# bus-main.net
KiCad netlist of a schematic drawn in Altium Designer
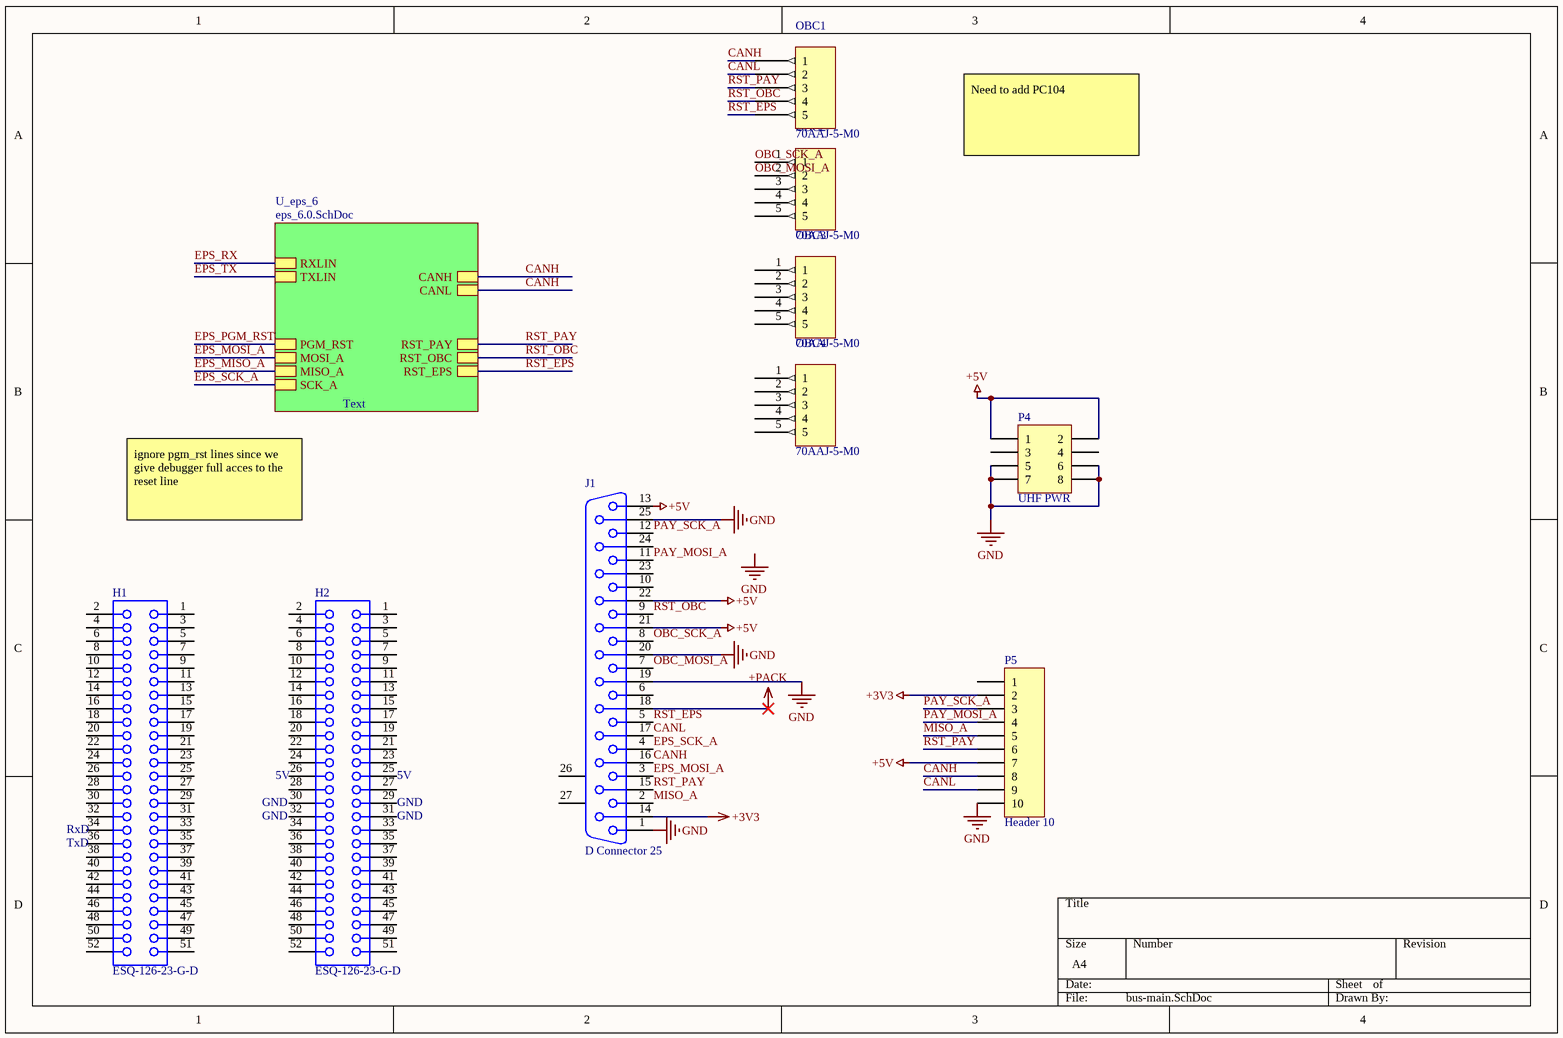
[diagram p0: bus-main.SchDoc]

(export (version "E")
  (design (tool "Eeschema 10.0.6"))
  (components
    (comp (ref "H1")
      (value "ESQ-126-23-G-D")
      (footprint "SMTC-ESQ-126-23-X-D")
      (fields (field (name "MANUFACTURER") "Samtec"))
      (libsource (lib "CONNs") (part "ESQ-126-23-G-D"))
    )
    (comp (ref "H2")
      (value "ESQ-126-23-G-D")
      (footprint "SMTC-ESQ-126-23-X-D")
      (fields (field (name "MANUFACTURER") "Samtec"))
      (libsource (lib "CONNs") (part "ESQ-126-23-G-D"))
    )
    (comp (ref "J1")
      (value "D Connector 25")
      (footprint "Mini DSub Connector")
      (description "Receptacle Assembly, 25 Position, Right Angle")
      (fields (field (name "PUBLISHER") "Altium Limited"))
      (libsource (lib "Miscellaneous Connectors") (part "D Connector 25"))
    )
    (comp (ref "OBC1") (value "70AAJ-5-M0") (libsource (lib "") (part "70AAJ-5-M0_1")))
    (comp (ref "OBC2") (value "70AAJ-5-M0") (libsource (lib "CONNs.") (part "70AAJ-5-M0")))
    (comp (ref "OBC3") (value "70AAJ-5-M0") (libsource (lib "CONNs.") (part "70AAJ-5-M0")))
    (comp (ref "OBC4") (value "70AAJ-5-M0") (libsource (lib "CONNs.") (part "70AAJ-5-M0")))
    (comp (ref "P4")
      (value "UHF PWR")
      (footprint "HDR2X4")
      (description "Header, 4-Pin, Dual row")
      (fields (field (name "PUBLISHER") "Altium Limited"))
      (libsource (lib "Miscellaneous Connectors") (part "Header 4X2"))
    )
    (comp (ref "P5")
      (value "Header 10")
      (footprint "DF14-10P-1.25H(55) - duplicate")
      (description "Header, 10-Pin")
      (fields (field (name "PUBLISHER") "Altium Limited"))
      (libsource (lib "Miscellaneous Connectors") (part "Header 10"))
    )
  )
  (nets
    (net (code "1") (name "+3V3") (class "Default")
      (node (ref "J1") (pin "14") (pinfunction "14_14") (pintype "passive"))
      (node (ref "P5") (pin "2") (pinfunction "2_2") (pintype "passive"))
    )
    (net (code "2") (name "+5V") (class "Default")
      (node (ref "J1") (pin "13") (pinfunction "13_13") (pintype "passive"))
      (node (ref "J1") (pin "21") (pinfunction "21_21") (pintype "passive"))
      (node (ref "J1") (pin "22") (pinfunction "22_22") (pintype "passive"))
      (node (ref "P4") (pin "1") (pinfunction "1_1") (pintype "passive"))
      (node (ref "P4") (pin "2") (pinfunction "2_2") (pintype "passive"))
      (node (ref "P5") (pin "7") (pinfunction "7_7") (pintype "passive"))
    )
    (net (code "3") (name "+PACK") (class "Default")
      (node (ref "J1") (pin "18") (pinfunction "18_18") (pintype "passive"))
    )
    (net (code "4") (name "/CANH") (class "Default")
      (node (ref "J1") (pin "16") (pinfunction "16_16") (pintype "passive"))
      (node (ref "OBC1") (pin "1") (pinfunction "1_1") (pintype "output"))
      (node (ref "P5") (pin "8") (pinfunction "8_8") (pintype "passive"))
    )
    (net (code "5") (name "/CANL") (class "Default")
      (node (ref "J1") (pin "17") (pinfunction "17_17") (pintype "passive"))
      (node (ref "OBC1") (pin "2") (pinfunction "2_2") (pintype "output"))
      (node (ref "P5") (pin "9") (pinfunction "9_9") (pintype "passive"))
    )
    (net (code "7") (name "/EPS_MOSI_A") (class "Default")
      (node (ref "J1") (pin "3") (pinfunction "3_3") (pintype "passive"))
    )
    (net (code "10") (name "/EPS_SCK_A") (class "Default")
      (node (ref "J1") (pin "4") (pinfunction "4_4") (pintype "passive"))
    )
    (net (code "12") (name "/MISO_A") (class "Default")
      (node (ref "J1") (pin "2") (pinfunction "2_2") (pintype "passive"))
      (node (ref "P5") (pin "5") (pinfunction "5_5") (pintype "passive"))
    )
    (net (code "13") (name "/OBC_MOSI_A") (class "Default")
      (node (ref "J1") (pin "7") (pinfunction "7_7") (pintype "passive"))
      (node (ref "OBC2") (pin "2") (pinfunction "2_2") (pintype "output"))
    )
    (net (code "14") (name "/OBC_SCK_A") (class "Default")
      (node (ref "J1") (pin "8") (pinfunction "8_8") (pintype "passive"))
      (node (ref "OBC2") (pin "1") (pinfunction "1_1") (pintype "output"))
    )
    (net (code "15") (name "/PAY_MOSI_A") (class "Default")
      (node (ref "J1") (pin "11") (pinfunction "11_11") (pintype "passive"))
      (node (ref "P5") (pin "4") (pinfunction "4_4") (pintype "passive"))
    )
    (net (code "16") (name "/PAY_SCK_A") (class "Default")
      (node (ref "J1") (pin "12") (pinfunction "12_12") (pintype "passive"))
      (node (ref "P5") (pin "3") (pinfunction "3_3") (pintype "passive"))
    )
    (net (code "17") (name "/RST_EPS") (class "Default")
      (node (ref "J1") (pin "5") (pinfunction "5_5") (pintype "passive"))
      (node (ref "OBC1") (pin "5") (pinfunction "5_5") (pintype "output"))
    )
    (net (code "18") (name "/RST_OBC") (class "Default")
      (node (ref "J1") (pin "9") (pinfunction "9_9") (pintype "passive"))
      (node (ref "OBC1") (pin "4") (pinfunction "4_4") (pintype "output"))
    )
    (net (code "19") (name "/RST_PAY") (class "Default")
      (node (ref "J1") (pin "15") (pinfunction "15_15") (pintype "passive"))
      (node (ref "OBC1") (pin "3") (pinfunction "3_3") (pintype "output"))
      (node (ref "P5") (pin "6") (pinfunction "6_6") (pintype "passive"))
    )
    (net (code "20") (name "GND") (class "Default")
      (node (ref "J1") (pin "1") (pinfunction "1_1") (pintype "passive"))
      (node (ref "J1") (pin "19") (pinfunction "19_19") (pintype "passive"))
      (node (ref "J1") (pin "20") (pinfunction "20_20") (pintype "passive"))
      (node (ref "J1") (pin "25") (pinfunction "25_25") (pintype "passive"))
      (node (ref "P4") (pin "5") (pinfunction "5_5") (pintype "passive"))
      (node (ref "P4") (pin "6") (pinfunction "6_6") (pintype "passive"))
      (node (ref "P4") (pin "7") (pinfunction "7_7") (pintype "passive"))
      (node (ref "P4") (pin "8") (pinfunction "8_8") (pintype "passive"))
      (node (ref "P5") (pin "10") (pinfunction "10_10") (pintype "passive"))
    )
    (net (code "21") (name "unconnected-(H1-Pad1)") (class "Default")
      (node (ref "H1") (pin "1") (pinfunction "1_1") (pintype "passive"))
    )
    (net (code "22") (name "unconnected-(H1-Pad2)") (class "Default")
      (node (ref "H1") (pin "2") (pinfunction "2_2") (pintype "passive"))
    )
    (net (code "23") (name "unconnected-(H1-Pad3)") (class "Default")
      (node (ref "H1") (pin "3") (pinfunction "3_3") (pintype "passive"))
    )
    (net (code "24") (name "unconnected-(H1-Pad4)") (class "Default")
      (node (ref "H1") (pin "4") (pinfunction "4_4") (pintype "passive"))
    )
    (net (code "25") (name "unconnected-(H1-Pad5)") (class "Default")
      (node (ref "H1") (pin "5") (pinfunction "5_5") (pintype "passive"))
    )
    (net (code "26") (name "unconnected-(H1-Pad6)") (class "Default")
      (node (ref "H1") (pin "6") (pinfunction "6_6") (pintype "passive"))
    )
    (net (code "27") (name "unconnected-(H1-Pad7)") (class "Default")
      (node (ref "H1") (pin "7") (pinfunction "7_7") (pintype "passive"))
    )
    (net (code "28") (name "unconnected-(H1-Pad8)") (class "Default")
      (node (ref "H1") (pin "8") (pinfunction "8_8") (pintype "passive"))
    )
    (net (code "29") (name "unconnected-(H1-Pad9)") (class "Default")
      (node (ref "H1") (pin "9") (pinfunction "9_9") (pintype "passive"))
    )
    (net (code "30") (name "unconnected-(H1-Pad10)") (class "Default")
      (node (ref "H1") (pin "10") (pinfunction "10_10") (pintype "passive"))
    )
    (net (code "31") (name "unconnected-(H1-Pad11)") (class "Default")
      (node (ref "H1") (pin "11") (pinfunction "11_11") (pintype "passive"))
    )
    (net (code "32") (name "unconnected-(H1-Pad12)") (class "Default")
      (node (ref "H1") (pin "12") (pinfunction "12_12") (pintype "passive"))
    )
    (net (code "33") (name "unconnected-(H1-Pad13)") (class "Default")
      (node (ref "H1") (pin "13") (pinfunction "13_13") (pintype "passive"))
    )
    (net (code "34") (name "unconnected-(H1-Pad14)") (class "Default")
      (node (ref "H1") (pin "14") (pinfunction "14_14") (pintype "passive"))
    )
    (net (code "35") (name "unconnected-(H1-Pad15)") (class "Default")
      (node (ref "H1") (pin "15") (pinfunction "15_15") (pintype "passive"))
    )
    (net (code "36") (name "unconnected-(H1-Pad16)") (class "Default")
      (node (ref "H1") (pin "16") (pinfunction "16_16") (pintype "passive"))
    )
    (net (code "37") (name "unconnected-(H1-Pad17)") (class "Default")
      (node (ref "H1") (pin "17") (pinfunction "17_17") (pintype "passive"))
    )
    (net (code "38") (name "unconnected-(H1-Pad18)") (class "Default")
      (node (ref "H1") (pin "18") (pinfunction "18_18") (pintype "passive"))
    )
    (net (code "39") (name "unconnected-(H1-Pad19)") (class "Default")
      (node (ref "H1") (pin "19") (pinfunction "19_19") (pintype "passive"))
    )
    (net (code "40") (name "unconnected-(H1-Pad20)") (class "Default")
      (node (ref "H1") (pin "20") (pinfunction "20_20") (pintype "passive"))
    )
    (net (code "41") (name "unconnected-(H1-Pad21)") (class "Default")
      (node (ref "H1") (pin "21") (pinfunction "21_21") (pintype "passive"))
    )
    (net (code "42") (name "unconnected-(H1-Pad22)") (class "Default")
      (node (ref "H1") (pin "22") (pinfunction "22_22") (pintype "passive"))
    )
    (net (code "43") (name "unconnected-(H1-Pad23)") (class "Default")
      (node (ref "H1") (pin "23") (pinfunction "23_23") (pintype "passive"))
    )
    (net (code "44") (name "unconnected-(H1-Pad24)") (class "Default")
      (node (ref "H1") (pin "24") (pinfunction "24_24") (pintype "passive"))
    )
    (net (code "45") (name "unconnected-(H1-Pad25)") (class "Default")
      (node (ref "H1") (pin "25") (pinfunction "25_25") (pintype "passive"))
    )
    (net (code "46") (name "unconnected-(H1-Pad26)") (class "Default")
      (node (ref "H1") (pin "26") (pinfunction "26_26") (pintype "passive"))
    )
    (net (code "47") (name "unconnected-(H1-Pad27)") (class "Default")
      (node (ref "H1") (pin "27") (pinfunction "27_27") (pintype "passive"))
    )
    (net (code "48") (name "unconnected-(H1-Pad28)") (class "Default")
      (node (ref "H1") (pin "28") (pinfunction "28_28") (pintype "passive"))
    )
    (net (code "49") (name "unconnected-(H1-Pad29)") (class "Default")
      (node (ref "H1") (pin "29") (pinfunction "29_29") (pintype "passive"))
    )
    (net (code "50") (name "unconnected-(H1-Pad30)") (class "Default")
      (node (ref "H1") (pin "30") (pinfunction "30_30") (pintype "passive"))
    )
    (net (code "51") (name "unconnected-(H1-Pad31)") (class "Default")
      (node (ref "H1") (pin "31") (pinfunction "31_31") (pintype "passive"))
    )
    (net (code "52") (name "unconnected-(H1-Pad32)") (class "Default")
      (node (ref "H1") (pin "32") (pinfunction "32_32") (pintype "passive"))
    )
    (net (code "53") (name "unconnected-(H1-Pad33)") (class "Default")
      (node (ref "H1") (pin "33") (pinfunction "33_33") (pintype "passive"))
    )
    (net (code "54") (name "unconnected-(H1-Pad34)") (class "Default")
      (node (ref "H1") (pin "34") (pinfunction "34_34") (pintype "passive"))
    )
    (net (code "55") (name "unconnected-(H1-Pad35)") (class "Default")
      (node (ref "H1") (pin "35") (pinfunction "35_35") (pintype "passive"))
    )
    (net (code "56") (name "unconnected-(H1-Pad36)") (class "Default")
      (node (ref "H1") (pin "36") (pinfunction "36_36") (pintype "passive"))
    )
    (net (code "57") (name "unconnected-(H1-Pad37)") (class "Default")
      (node (ref "H1") (pin "37") (pinfunction "37_37") (pintype "passive"))
    )
    (net (code "58") (name "unconnected-(H1-Pad38)") (class "Default")
      (node (ref "H1") (pin "38") (pinfunction "38_38") (pintype "passive"))
    )
    (net (code "59") (name "unconnected-(H1-Pad39)") (class "Default")
      (node (ref "H1") (pin "39") (pinfunction "39_39") (pintype "passive"))
    )
    (net (code "60") (name "unconnected-(H1-Pad40)") (class "Default")
      (node (ref "H1") (pin "40") (pinfunction "40_40") (pintype "passive"))
    )
    (net (code "61") (name "unconnected-(H1-Pad41)") (class "Default")
      (node (ref "H1") (pin "41") (pinfunction "41_41") (pintype "passive"))
    )
    (net (code "62") (name "unconnected-(H1-Pad42)") (class "Default")
      (node (ref "H1") (pin "42") (pinfunction "42_42") (pintype "passive"))
    )
    (net (code "63") (name "unconnected-(H1-Pad43)") (class "Default")
      (node (ref "H1") (pin "43") (pinfunction "43_43") (pintype "passive"))
    )
    (net (code "64") (name "unconnected-(H1-Pad44)") (class "Default")
      (node (ref "H1") (pin "44") (pinfunction "44_44") (pintype "passive"))
    )
    (net (code "65") (name "unconnected-(H1-Pad45)") (class "Default")
      (node (ref "H1") (pin "45") (pinfunction "45_45") (pintype "passive"))
    )
    (net (code "66") (name "unconnected-(H1-Pad46)") (class "Default")
      (node (ref "H1") (pin "46") (pinfunction "46_46") (pintype "passive"))
    )
    (net (code "67") (name "unconnected-(H1-Pad47)") (class "Default")
      (node (ref "H1") (pin "47") (pinfunction "47_47") (pintype "passive"))
    )
    (net (code "68") (name "unconnected-(H1-Pad48)") (class "Default")
      (node (ref "H1") (pin "48") (pinfunction "48_48") (pintype "passive"))
    )
    (net (code "69") (name "unconnected-(H1-Pad49)") (class "Default")
      (node (ref "H1") (pin "49") (pinfunction "49_49") (pintype "passive"))
    )
    (net (code "70") (name "unconnected-(H1-Pad50)") (class "Default")
      (node (ref "H1") (pin "50") (pinfunction "50_50") (pintype "passive"))
    )
    (net (code "71") (name "unconnected-(H1-Pad51)") (class "Default")
      (node (ref "H1") (pin "51") (pinfunction "51_51") (pintype "passive"))
    )
    (net (code "72") (name "unconnected-(H1-Pad52)") (class "Default")
      (node (ref "H1") (pin "52") (pinfunction "52_52") (pintype "passive"))
    )
    (net (code "73") (name "unconnected-(H2-Pad1)") (class "Default")
      (node (ref "H2") (pin "1") (pinfunction "1_1") (pintype "passive"))
    )
    (net (code "74") (name "unconnected-(H2-Pad2)") (class "Default")
      (node (ref "H2") (pin "2") (pinfunction "2_2") (pintype "passive"))
    )
    (net (code "75") (name "unconnected-(H2-Pad3)") (class "Default")
      (node (ref "H2") (pin "3") (pinfunction "3_3") (pintype "passive"))
    )
    (net (code "76") (name "unconnected-(H2-Pad4)") (class "Default")
      (node (ref "H2") (pin "4") (pinfunction "4_4") (pintype "passive"))
    )
    (net (code "77") (name "unconnected-(H2-Pad5)") (class "Default")
      (node (ref "H2") (pin "5") (pinfunction "5_5") (pintype "passive"))
    )
    (net (code "78") (name "unconnected-(H2-Pad6)") (class "Default")
      (node (ref "H2") (pin "6") (pinfunction "6_6") (pintype "passive"))
    )
    (net (code "79") (name "unconnected-(H2-Pad7)") (class "Default")
      (node (ref "H2") (pin "7") (pinfunction "7_7") (pintype "passive"))
    )
    (net (code "80") (name "unconnected-(H2-Pad8)") (class "Default")
      (node (ref "H2") (pin "8") (pinfunction "8_8") (pintype "passive"))
    )
    (net (code "81") (name "unconnected-(H2-Pad9)") (class "Default")
      (node (ref "H2") (pin "9") (pinfunction "9_9") (pintype "passive"))
    )
    (net (code "82") (name "unconnected-(H2-Pad10)") (class "Default")
      (node (ref "H2") (pin "10") (pinfunction "10_10") (pintype "passive"))
    )
    (net (code "83") (name "unconnected-(H2-Pad11)") (class "Default")
      (node (ref "H2") (pin "11") (pinfunction "11_11") (pintype "passive"))
    )
    (net (code "84") (name "unconnected-(H2-Pad12)") (class "Default")
      (node (ref "H2") (pin "12") (pinfunction "12_12") (pintype "passive"))
    )
    (net (code "85") (name "unconnected-(H2-Pad13)") (class "Default")
      (node (ref "H2") (pin "13") (pinfunction "13_13") (pintype "passive"))
    )
    (net (code "86") (name "unconnected-(H2-Pad14)") (class "Default")
      (node (ref "H2") (pin "14") (pinfunction "14_14") (pintype "passive"))
    )
    (net (code "87") (name "unconnected-(H2-Pad15)") (class "Default")
      (node (ref "H2") (pin "15") (pinfunction "15_15") (pintype "passive"))
    )
    (net (code "88") (name "unconnected-(H2-Pad16)") (class "Default")
      (node (ref "H2") (pin "16") (pinfunction "16_16") (pintype "passive"))
    )
    (net (code "89") (name "unconnected-(H2-Pad17)") (class "Default")
      (node (ref "H2") (pin "17") (pinfunction "17_17") (pintype "passive"))
    )
    (net (code "90") (name "unconnected-(H2-Pad18)") (class "Default")
      (node (ref "H2") (pin "18") (pinfunction "18_18") (pintype "passive"))
    )
    (net (code "91") (name "unconnected-(H2-Pad19)") (class "Default")
      (node (ref "H2") (pin "19") (pinfunction "19_19") (pintype "passive"))
    )
    (net (code "92") (name "unconnected-(H2-Pad20)") (class "Default")
      (node (ref "H2") (pin "20") (pinfunction "20_20") (pintype "passive"))
    )
    (net (code "93") (name "unconnected-(H2-Pad21)") (class "Default")
      (node (ref "H2") (pin "21") (pinfunction "21_21") (pintype "passive"))
    )
    (net (code "94") (name "unconnected-(H2-Pad22)") (class "Default")
      (node (ref "H2") (pin "22") (pinfunction "22_22") (pintype "passive"))
    )
    (net (code "95") (name "unconnected-(H2-Pad23)") (class "Default")
      (node (ref "H2") (pin "23") (pinfunction "23_23") (pintype "passive"))
    )
    (net (code "96") (name "unconnected-(H2-Pad24)") (class "Default")
      (node (ref "H2") (pin "24") (pinfunction "24_24") (pintype "passive"))
    )
    (net (code "97") (name "unconnected-(H2-Pad25)") (class "Default")
      (node (ref "H2") (pin "25") (pinfunction "25_25") (pintype "passive"))
    )
    (net (code "98") (name "unconnected-(H2-Pad26)") (class "Default")
      (node (ref "H2") (pin "26") (pinfunction "26_26") (pintype "passive"))
    )
    (net (code "99") (name "unconnected-(H2-Pad27)") (class "Default")
      (node (ref "H2") (pin "27") (pinfunction "27_27") (pintype "passive"))
    )
    (net (code "100") (name "unconnected-(H2-Pad28)") (class "Default")
      (node (ref "H2") (pin "28") (pinfunction "28_28") (pintype "passive"))
    )
    (net (code "101") (name "unconnected-(H2-Pad29)") (class "Default")
      (node (ref "H2") (pin "29") (pinfunction "29_29") (pintype "passive"))
    )
    (net (code "102") (name "unconnected-(H2-Pad30)") (class "Default")
      (node (ref "H2") (pin "30") (pinfunction "30_30") (pintype "passive"))
    )
    (net (code "103") (name "unconnected-(H2-Pad31)") (class "Default")
      (node (ref "H2") (pin "31") (pinfunction "31_31") (pintype "passive"))
    )
    (net (code "104") (name "unconnected-(H2-Pad32)") (class "Default")
      (node (ref "H2") (pin "32") (pinfunction "32_32") (pintype "passive"))
    )
    (net (code "105") (name "unconnected-(H2-Pad33)") (class "Default")
      (node (ref "H2") (pin "33") (pinfunction "33_33") (pintype "passive"))
    )
    (net (code "106") (name "unconnected-(H2-Pad34)") (class "Default")
      (node (ref "H2") (pin "34") (pinfunction "34_34") (pintype "passive"))
    )
    (net (code "107") (name "unconnected-(H2-Pad35)") (class "Default")
      (node (ref "H2") (pin "35") (pinfunction "35_35") (pintype "passive"))
    )
    (net (code "108") (name "unconnected-(H2-Pad36)") (class "Default")
      (node (ref "H2") (pin "36") (pinfunction "36_36") (pintype "passive"))
    )
    (net (code "109") (name "unconnected-(H2-Pad37)") (class "Default")
      (node (ref "H2") (pin "37") (pinfunction "37_37") (pintype "passive"))
    )
    (net (code "110") (name "unconnected-(H2-Pad38)") (class "Default")
      (node (ref "H2") (pin "38") (pinfunction "38_38") (pintype "passive"))
    )
    (net (code "111") (name "unconnected-(H2-Pad39)") (class "Default")
      (node (ref "H2") (pin "39") (pinfunction "39_39") (pintype "passive"))
    )
    (net (code "112") (name "unconnected-(H2-Pad40)") (class "Default")
      (node (ref "H2") (pin "40") (pinfunction "40_40") (pintype "passive"))
    )
    (net (code "113") (name "unconnected-(H2-Pad41)") (class "Default")
      (node (ref "H2") (pin "41") (pinfunction "41_41") (pintype "passive"))
    )
    (net (code "114") (name "unconnected-(H2-Pad42)") (class "Default")
      (node (ref "H2") (pin "42") (pinfunction "42_42") (pintype "passive"))
    )
    (net (code "115") (name "unconnected-(H2-Pad43)") (class "Default")
      (node (ref "H2") (pin "43") (pinfunction "43_43") (pintype "passive"))
    )
    (net (code "116") (name "unconnected-(H2-Pad44)") (class "Default")
      (node (ref "H2") (pin "44") (pinfunction "44_44") (pintype "passive"))
    )
    (net (code "117") (name "unconnected-(H2-Pad45)") (class "Default")
      (node (ref "H2") (pin "45") (pinfunction "45_45") (pintype "passive"))
    )
    (net (code "118") (name "unconnected-(H2-Pad46)") (class "Default")
      (node (ref "H2") (pin "46") (pinfunction "46_46") (pintype "passive"))
    )
    (net (code "119") (name "unconnected-(H2-Pad47)") (class "Default")
      (node (ref "H2") (pin "47") (pinfunction "47_47") (pintype "passive"))
    )
    (net (code "120") (name "unconnected-(H2-Pad48)") (class "Default")
      (node (ref "H2") (pin "48") (pinfunction "48_48") (pintype "passive"))
    )
    (net (code "121") (name "unconnected-(H2-Pad49)") (class "Default")
      (node (ref "H2") (pin "49") (pinfunction "49_49") (pintype "passive"))
    )
    (net (code "122") (name "unconnected-(H2-Pad50)") (class "Default")
      (node (ref "H2") (pin "50") (pinfunction "50_50") (pintype "passive"))
    )
    (net (code "123") (name "unconnected-(H2-Pad51)") (class "Default")
      (node (ref "H2") (pin "51") (pinfunction "51_51") (pintype "passive"))
    )
    (net (code "124") (name "unconnected-(H2-Pad52)") (class "Default")
      (node (ref "H2") (pin "52") (pinfunction "52_52") (pintype "passive"))
    )
    (net (code "125") (name "unconnected-(J1-MH1-Pad26)") (class "Default")
      (node (ref "J1") (pin "26") (pinfunction "MH1_26") (pintype "passive"))
    )
    (net (code "126") (name "unconnected-(J1-MH2-Pad27)") (class "Default")
      (node (ref "J1") (pin "27") (pinfunction "MH2_27") (pintype "passive"))
    )
    (net (code "127") (name "unconnected-(J1-Pad6)") (class "Default")
      (node (ref "J1") (pin "6") (pinfunction "6_6") (pintype "passive"))
    )
    (net (code "128") (name "unconnected-(J1-Pad10)") (class "Default")
      (node (ref "J1") (pin "10") (pinfunction "10_10") (pintype "passive"))
    )
    (net (code "129") (name "unconnected-(J1-Pad23)") (class "Default")
      (node (ref "J1") (pin "23") (pinfunction "23_23") (pintype "passive"))
    )
    (net (code "130") (name "unconnected-(J1-Pad24)") (class "Default")
      (node (ref "J1") (pin "24") (pinfunction "24_24") (pintype "passive"))
    )
    (net (code "131") (name "unconnected-(OBC2-Pad3)") (class "Default")
      (node (ref "OBC2") (pin "3") (pinfunction "3_3") (pintype "output"))
    )
    (net (code "132") (name "unconnected-(OBC2-Pad4)") (class "Default")
      (node (ref "OBC2") (pin "4") (pinfunction "4_4") (pintype "output"))
    )
    (net (code "133") (name "unconnected-(OBC2-Pad5)") (class "Default")
      (node (ref "OBC2") (pin "5") (pinfunction "5_5") (pintype "output"))
    )
    (net (code "134") (name "unconnected-(OBC3-Pad1)") (class "Default")
      (node (ref "OBC3") (pin "1") (pinfunction "1_1") (pintype "output"))
    )
    (net (code "135") (name "unconnected-(OBC3-Pad2)") (class "Default")
      (node (ref "OBC3") (pin "2") (pinfunction "2_2") (pintype "output"))
    )
    (net (code "136") (name "unconnected-(OBC3-Pad3)") (class "Default")
      (node (ref "OBC3") (pin "3") (pinfunction "3_3") (pintype "output"))
    )
    (net (code "137") (name "unconnected-(OBC3-Pad4)") (class "Default")
      (node (ref "OBC3") (pin "4") (pinfunction "4_4") (pintype "output"))
    )
    (net (code "138") (name "unconnected-(OBC3-Pad5)") (class "Default")
      (node (ref "OBC3") (pin "5") (pinfunction "5_5") (pintype "output"))
    )
    (net (code "139") (name "unconnected-(OBC4-Pad1)") (class "Default")
      (node (ref "OBC4") (pin "1") (pinfunction "1_1") (pintype "output"))
    )
    (net (code "140") (name "unconnected-(OBC4-Pad2)") (class "Default")
      (node (ref "OBC4") (pin "2") (pinfunction "2_2") (pintype "output"))
    )
    (net (code "141") (name "unconnected-(OBC4-Pad3)") (class "Default")
      (node (ref "OBC4") (pin "3") (pinfunction "3_3") (pintype "output"))
    )
    (net (code "142") (name "unconnected-(OBC4-Pad4)") (class "Default")
      (node (ref "OBC4") (pin "4") (pinfunction "4_4") (pintype "output"))
    )
    (net (code "143") (name "unconnected-(OBC4-Pad5)") (class "Default")
      (node (ref "OBC4") (pin "5") (pinfunction "5_5") (pintype "output"))
    )
    (net (code "144") (name "unconnected-(P4-Pad3)") (class "Default")
      (node (ref "P4") (pin "3") (pinfunction "3_3") (pintype "passive"))
    )
    (net (code "145") (name "unconnected-(P4-Pad4)") (class "Default")
      (node (ref "P4") (pin "4") (pinfunction "4_4") (pintype "passive"))
    )
    (net (code "146") (name "unconnected-(P5-Pad1)") (class "Default")
      (node (ref "P5") (pin "1") (pinfunction "1_1") (pintype "passive"))
    )
  )
)
